# 7segement4digits1badidea-huge-digits-mk-.net
KiCad netlist of a schematic drawn in EAGLE
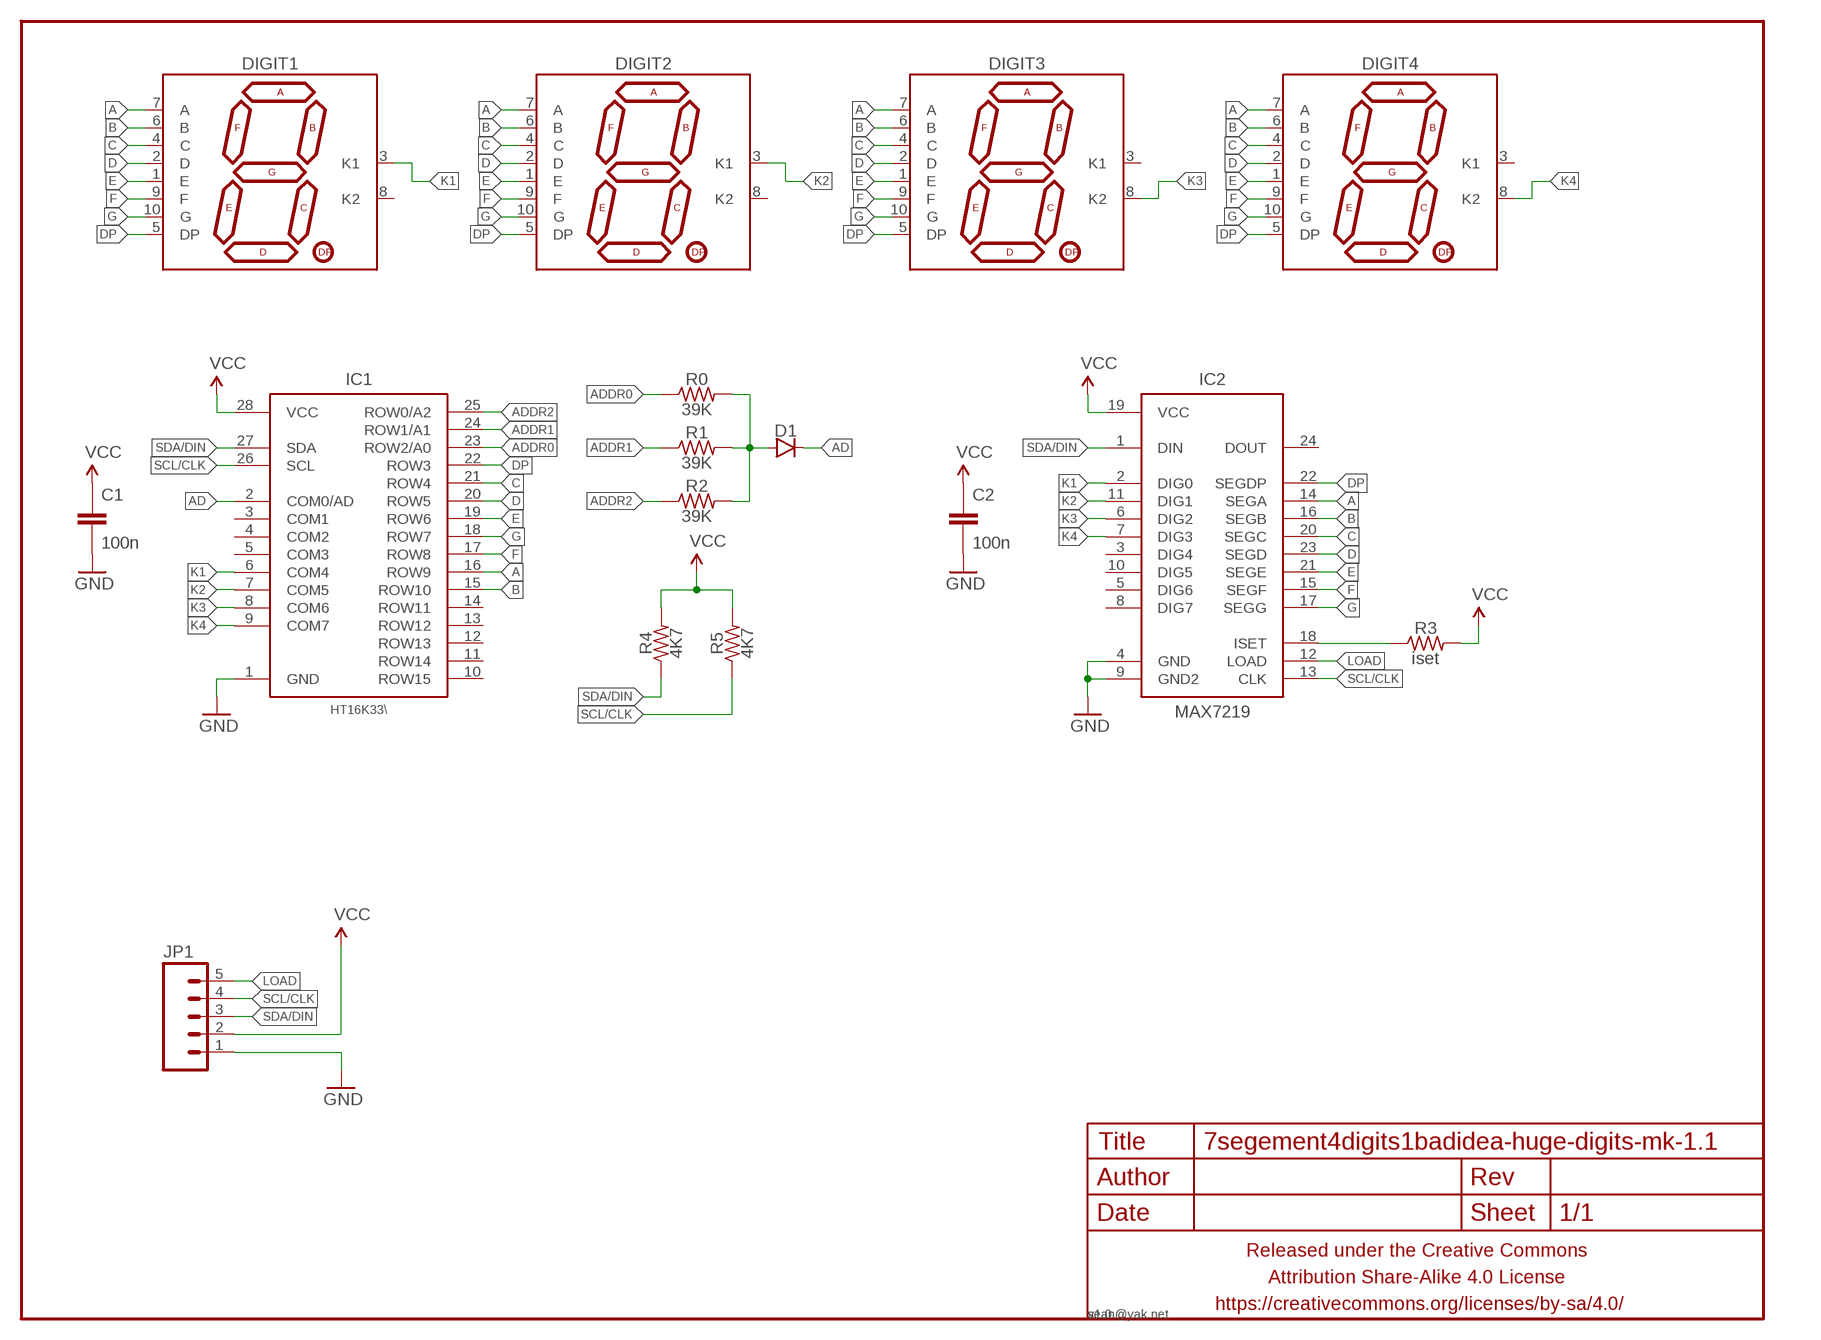
[diagram p0: schematic, sheet 1]

(export (version "E")
  (design (tool "Eeschema 10.0.6"))
  (components
    (comp (ref "C1")
      (value "100n")
      (footprint "eagle-import:C0805")
      (libsource (lib "eagle-import") (part "CAPACITOR-CERAMICC0805"))
    )
    (comp (ref "C2")
      (value "100n")
      (footprint "eagle-import:C0805")
      (libsource (lib "eagle-import") (part "CAPACITOR-CERAMICC0805"))
    )
    (comp (ref "D1")
      (value "DIODESOD123")
      (footprint "eagle-import:SOD123")
      (libsource (lib "eagle-import") (part "DIODESOD123"))
    )
    (comp (ref "DIGIT1")
      (value "7SEG_1DIGPTH-25.4MM")
      (footprint "eagle-import:7SEG_1DIG_25.4MM")
      (libsource (lib "eagle-import") (part "7SEG_1DIGPTH-25.4MM"))
    )
    (comp (ref "DIGIT2")
      (value "7SEG_1DIGPTH-25.4MM")
      (footprint "eagle-import:7SEG_1DIG_25.4MM")
      (libsource (lib "eagle-import") (part "7SEG_1DIGPTH-25.4MM"))
    )
    (comp (ref "DIGIT3")
      (value "7SEG_1DIGPTH-25.4MM")
      (footprint "eagle-import:7SEG_1DIG_25.4MM")
      (libsource (lib "eagle-import") (part "7SEG_1DIGPTH-25.4MM"))
    )
    (comp (ref "DIGIT4")
      (value "7SEG_1DIGPTH-25.4MM")
      (footprint "eagle-import:7SEG_1DIG_25.4MM")
      (libsource (lib "eagle-import") (part "7SEG_1DIGPTH-25.4MM"))
    )
    (comp (ref "FRAME1")
      (value "FRAME-LETTERNO_PACKAGE")
      (footprint "eagle-import:DUMMY")
      (fields
        (field (name "DESIGNER") "Nobody")
        (field (name "VERSION") "v01")
        (field (name "DESIGNER_1") "sean@yak.net")
        (field (name "VERSION_1") "v1.0")
      )
      (libsource (lib "eagle-import") (part "FRAME-LETTERNO_PACKAGE"))
    )
    (comp (ref "IC1")
      (value "HT16K33\\")
      (footprint "eagle-import:SOIC28W")
      (libsource (lib "eagle-import") (part "HT16K33-28SOIC28W"))
    )
    (comp (ref "IC2")
      (value "MAX7219")
      (footprint "eagle-import:SO24W")
      (libsource (lib "eagle-import") (part "MAX7219SOIC-W"))
    )
    (comp (ref "JP1")
      (value "M05PTH-CENTERED")
      (footprint "eagle-import:1X05_PTH_CENTERED")
      (libsource (lib "eagle-import") (part "M05PTH-CENTERED"))
    )
    (comp (ref "R0")
      (value "39K")
      (footprint "eagle-import:R0805")
      (libsource (lib "eagle-import") (part "RESISTORR0805"))
    )
    (comp (ref "R1")
      (value "39K")
      (footprint "eagle-import:R0805")
      (libsource (lib "eagle-import") (part "RESISTORR0805"))
    )
    (comp (ref "R2")
      (value "39K")
      (footprint "eagle-import:R0805")
      (libsource (lib "eagle-import") (part "RESISTORR0805"))
    )
    (comp (ref "R3")
      (value "iset")
      (footprint "eagle-import:R0805")
      (libsource (lib "eagle-import") (part "RESISTORR0805"))
    )
    (comp (ref "R4")
      (value "4K7")
      (footprint "eagle-import:R0805")
      (libsource (lib "eagle-import") (part "RESISTORR0805"))
    )
    (comp (ref "R5")
      (value "4K7")
      (footprint "eagle-import:R0805")
      (libsource (lib "eagle-import") (part "RESISTORR0805"))
    )
  )
  (nets
    (net (code "1") (name "A") (class "Default")
      (node (ref "DIGIT1") (pin "7") (pinfunction "A_7") (pintype "bidirectional"))
      (node (ref "DIGIT2") (pin "7") (pinfunction "A_7") (pintype "bidirectional"))
      (node (ref "DIGIT3") (pin "7") (pinfunction "A_7") (pintype "bidirectional"))
      (node (ref "DIGIT4") (pin "7") (pinfunction "A_7") (pintype "bidirectional"))
      (node (ref "IC1") (pin "16") (pinfunction "ROW9_16") (pintype "bidirectional"))
      (node (ref "IC2") (pin "14") (pinfunction "SEGA_14") (pintype "bidirectional"))
    )
    (net (code "2") (name "AD") (class "Default")
      (node (ref "D1") (pin "C") (pinfunction "C_C") (pintype "passive"))
      (node (ref "IC1") (pin "2") (pinfunction "COM0/AD_2") (pintype "bidirectional"))
    )
    (net (code "3") (name "ADDR0") (class "Default")
      (node (ref "IC1") (pin "23") (pinfunction "ROW2/A0_23") (pintype "bidirectional"))
      (node (ref "R0") (pin "1") (pinfunction "1_1") (pintype "passive"))
    )
    (net (code "4") (name "ADDR1") (class "Default")
      (node (ref "IC1") (pin "24") (pinfunction "ROW1/A1_24") (pintype "bidirectional"))
      (node (ref "R1") (pin "1") (pinfunction "1_1") (pintype "passive"))
    )
    (net (code "5") (name "ADDR2") (class "Default")
      (node (ref "IC1") (pin "25") (pinfunction "ROW0/A2_25") (pintype "bidirectional"))
      (node (ref "R2") (pin "1") (pinfunction "1_1") (pintype "passive"))
    )
    (net (code "6") (name "B") (class "Default")
      (node (ref "DIGIT1") (pin "6") (pinfunction "B_6") (pintype "bidirectional"))
      (node (ref "DIGIT2") (pin "6") (pinfunction "B_6") (pintype "bidirectional"))
      (node (ref "DIGIT3") (pin "6") (pinfunction "B_6") (pintype "bidirectional"))
      (node (ref "DIGIT4") (pin "6") (pinfunction "B_6") (pintype "bidirectional"))
      (node (ref "IC1") (pin "15") (pinfunction "ROW10_15") (pintype "bidirectional"))
      (node (ref "IC2") (pin "16") (pinfunction "SEGB_16") (pintype "bidirectional"))
    )
    (net (code "7") (name "C") (class "Default")
      (node (ref "DIGIT1") (pin "4") (pinfunction "C_4") (pintype "bidirectional"))
      (node (ref "DIGIT2") (pin "4") (pinfunction "C_4") (pintype "bidirectional"))
      (node (ref "DIGIT3") (pin "4") (pinfunction "C_4") (pintype "bidirectional"))
      (node (ref "DIGIT4") (pin "4") (pinfunction "C_4") (pintype "bidirectional"))
      (node (ref "IC1") (pin "21") (pinfunction "ROW4_21") (pintype "bidirectional"))
      (node (ref "IC2") (pin "20") (pinfunction "SEGC_20") (pintype "bidirectional"))
    )
    (net (code "8") (name "D") (class "Default")
      (node (ref "DIGIT1") (pin "2") (pinfunction "D_2") (pintype "bidirectional"))
      (node (ref "DIGIT2") (pin "2") (pinfunction "D_2") (pintype "bidirectional"))
      (node (ref "DIGIT3") (pin "2") (pinfunction "D_2") (pintype "bidirectional"))
      (node (ref "DIGIT4") (pin "2") (pinfunction "D_2") (pintype "bidirectional"))
      (node (ref "IC1") (pin "20") (pinfunction "ROW5_20") (pintype "bidirectional"))
      (node (ref "IC2") (pin "23") (pinfunction "SEGD_23") (pintype "bidirectional"))
    )
    (net (code "9") (name "DP") (class "Default")
      (node (ref "DIGIT1") (pin "5") (pinfunction "DP_5") (pintype "bidirectional"))
      (node (ref "DIGIT2") (pin "5") (pinfunction "DP_5") (pintype "bidirectional"))
      (node (ref "DIGIT3") (pin "5") (pinfunction "DP_5") (pintype "bidirectional"))
      (node (ref "DIGIT4") (pin "5") (pinfunction "DP_5") (pintype "bidirectional"))
      (node (ref "IC1") (pin "22") (pinfunction "ROW3_22") (pintype "bidirectional"))
      (node (ref "IC2") (pin "22") (pinfunction "SEGDP_22") (pintype "bidirectional"))
    )
    (net (code "10") (name "E") (class "Default")
      (node (ref "DIGIT1") (pin "1") (pinfunction "E_1") (pintype "bidirectional"))
      (node (ref "DIGIT2") (pin "1") (pinfunction "E_1") (pintype "bidirectional"))
      (node (ref "DIGIT3") (pin "1") (pinfunction "E_1") (pintype "bidirectional"))
      (node (ref "DIGIT4") (pin "1") (pinfunction "E_1") (pintype "bidirectional"))
      (node (ref "IC1") (pin "19") (pinfunction "ROW6_19") (pintype "bidirectional"))
      (node (ref "IC2") (pin "21") (pinfunction "SEGE_21") (pintype "bidirectional"))
    )
    (net (code "11") (name "F") (class "Default")
      (node (ref "DIGIT1") (pin "9") (pinfunction "F_9") (pintype "bidirectional"))
      (node (ref "DIGIT2") (pin "9") (pinfunction "F_9") (pintype "bidirectional"))
      (node (ref "DIGIT3") (pin "9") (pinfunction "F_9") (pintype "bidirectional"))
      (node (ref "DIGIT4") (pin "9") (pinfunction "F_9") (pintype "bidirectional"))
      (node (ref "IC1") (pin "17") (pinfunction "ROW8_17") (pintype "bidirectional"))
      (node (ref "IC2") (pin "15") (pinfunction "SEGF_15") (pintype "bidirectional"))
    )
    (net (code "12") (name "G") (class "Default")
      (node (ref "DIGIT1") (pin "10") (pinfunction "G_10") (pintype "bidirectional"))
      (node (ref "DIGIT2") (pin "10") (pinfunction "G_10") (pintype "bidirectional"))
      (node (ref "DIGIT3") (pin "10") (pinfunction "G_10") (pintype "bidirectional"))
      (node (ref "DIGIT4") (pin "10") (pinfunction "G_10") (pintype "bidirectional"))
      (node (ref "IC1") (pin "18") (pinfunction "ROW7_18") (pintype "bidirectional"))
      (node (ref "IC2") (pin "17") (pinfunction "SEGG_17") (pintype "bidirectional"))
    )
    (net (code "13") (name "GND") (class "Default")
      (node (ref "C1") (pin "2") (pinfunction "2_2") (pintype "passive"))
      (node (ref "C2") (pin "2") (pinfunction "2_2") (pintype "passive"))
      (node (ref "IC1") (pin "1") (pinfunction "GND_1") (pintype "bidirectional"))
      (node (ref "IC2") (pin "4") (pinfunction "GND_4") (pintype "bidirectional"))
      (node (ref "IC2") (pin "9") (pinfunction "GND2_9") (pintype "bidirectional"))
      (node (ref "JP1") (pin "1") (pinfunction "1_1") (pintype "passive"))
    )
    (net (code "14") (name "K1") (class "Default")
      (node (ref "DIGIT1") (pin "3") (pinfunction "K1_3") (pintype "bidirectional"))
      (node (ref "IC1") (pin "6") (pinfunction "COM4_6") (pintype "bidirectional"))
      (node (ref "IC2") (pin "2") (pinfunction "DIG0_2") (pintype "bidirectional"))
    )
    (net (code "15") (name "K2") (class "Default")
      (node (ref "DIGIT2") (pin "3") (pinfunction "K1_3") (pintype "bidirectional"))
      (node (ref "IC1") (pin "7") (pinfunction "COM5_7") (pintype "bidirectional"))
      (node (ref "IC2") (pin "11") (pinfunction "DIG1_11") (pintype "bidirectional"))
    )
    (net (code "16") (name "K3") (class "Default")
      (node (ref "DIGIT3") (pin "8") (pinfunction "K2_8") (pintype "bidirectional"))
      (node (ref "IC1") (pin "8") (pinfunction "COM6_8") (pintype "bidirectional"))
      (node (ref "IC2") (pin "6") (pinfunction "DIG2_6") (pintype "bidirectional"))
    )
    (net (code "17") (name "K4") (class "Default")
      (node (ref "DIGIT4") (pin "8") (pinfunction "K2_8") (pintype "bidirectional"))
      (node (ref "IC1") (pin "9") (pinfunction "COM7_9") (pintype "bidirectional"))
      (node (ref "IC2") (pin "7") (pinfunction "DIG3_7") (pintype "bidirectional"))
    )
    (net (code "18") (name "LOAD") (class "Default")
      (node (ref "IC2") (pin "12") (pinfunction "LOAD_12") (pintype "bidirectional"))
      (node (ref "JP1") (pin "5") (pinfunction "5_5") (pintype "passive"))
    )
    (net (code "19") (name "Net-(D1-PadA)") (class "Default")
      (node (ref "D1") (pin "A") (pinfunction "A_A") (pintype "passive"))
      (node (ref "R0") (pin "2") (pinfunction "2_2") (pintype "passive"))
      (node (ref "R1") (pin "2") (pinfunction "2_2") (pintype "passive"))
      (node (ref "R2") (pin "2") (pinfunction "2_2") (pintype "passive"))
    )
    (net (code "20") (name "Net-(IC2-ISET)") (class "Default")
      (node (ref "IC2") (pin "18") (pinfunction "ISET_18") (pintype "bidirectional"))
      (node (ref "R3") (pin "1") (pinfunction "1_1") (pintype "passive"))
    )
    (net (code "21") (name "SCL{slash}CLK") (class "Default")
      (node (ref "IC1") (pin "26") (pinfunction "SCL_26") (pintype "bidirectional"))
      (node (ref "IC2") (pin "13") (pinfunction "CLK_13") (pintype "bidirectional"))
      (node (ref "JP1") (pin "4") (pinfunction "4_4") (pintype "passive"))
      (node (ref "R5") (pin "1") (pinfunction "1_1") (pintype "passive"))
    )
    (net (code "22") (name "SDA{slash}DIN") (class "Default")
      (node (ref "IC1") (pin "27") (pinfunction "SDA_27") (pintype "bidirectional"))
      (node (ref "IC2") (pin "1") (pinfunction "DIN_1") (pintype "bidirectional"))
      (node (ref "JP1") (pin "3") (pinfunction "3_3") (pintype "passive"))
      (node (ref "R4") (pin "1") (pinfunction "1_1") (pintype "passive"))
    )
    (net (code "23") (name "VCC") (class "Default")
      (node (ref "C1") (pin "1") (pinfunction "1_1") (pintype "passive"))
      (node (ref "C2") (pin "1") (pinfunction "1_1") (pintype "passive"))
      (node (ref "IC1") (pin "28") (pinfunction "VCC_28") (pintype "bidirectional"))
      (node (ref "IC2") (pin "19") (pinfunction "VCC_19") (pintype "bidirectional"))
      (node (ref "JP1") (pin "2") (pinfunction "2_2") (pintype "passive"))
      (node (ref "R3") (pin "2") (pinfunction "2_2") (pintype "passive"))
      (node (ref "R4") (pin "2") (pinfunction "2_2") (pintype "passive"))
      (node (ref "R5") (pin "2") (pinfunction "2_2") (pintype "passive"))
    )
    (net (code "24") (name "unconnected-(DIGIT1-K2-Pad8)") (class "Default")
      (node (ref "DIGIT1") (pin "8") (pinfunction "K2_8") (pintype "bidirectional"))
    )
    (net (code "25") (name "unconnected-(DIGIT2-K2-Pad8)") (class "Default")
      (node (ref "DIGIT2") (pin "8") (pinfunction "K2_8") (pintype "bidirectional"))
    )
    (net (code "26") (name "unconnected-(DIGIT3-K1-Pad3)") (class "Default")
      (node (ref "DIGIT3") (pin "3") (pinfunction "K1_3") (pintype "bidirectional"))
    )
    (net (code "27") (name "unconnected-(DIGIT4-K1-Pad3)") (class "Default")
      (node (ref "DIGIT4") (pin "3") (pinfunction "K1_3") (pintype "bidirectional"))
    )
    (net (code "28") (name "unconnected-(IC1-COM1-Pad3)") (class "Default")
      (node (ref "IC1") (pin "3") (pinfunction "COM1_3") (pintype "bidirectional"))
    )
    (net (code "29") (name "unconnected-(IC1-COM2-Pad4)") (class "Default")
      (node (ref "IC1") (pin "4") (pinfunction "COM2_4") (pintype "bidirectional"))
    )
    (net (code "30") (name "unconnected-(IC1-COM3-Pad5)") (class "Default")
      (node (ref "IC1") (pin "5") (pinfunction "COM3_5") (pintype "bidirectional"))
    )
    (net (code "31") (name "unconnected-(IC1-ROW11-Pad14)") (class "Default")
      (node (ref "IC1") (pin "14") (pinfunction "ROW11_14") (pintype "bidirectional"))
    )
    (net (code "32") (name "unconnected-(IC1-ROW12-Pad13)") (class "Default")
      (node (ref "IC1") (pin "13") (pinfunction "ROW12_13") (pintype "bidirectional"))
    )
    (net (code "33") (name "unconnected-(IC1-ROW13-Pad12)") (class "Default")
      (node (ref "IC1") (pin "12") (pinfunction "ROW13_12") (pintype "bidirectional"))
    )
    (net (code "34") (name "unconnected-(IC1-ROW14-Pad11)") (class "Default")
      (node (ref "IC1") (pin "11") (pinfunction "ROW14_11") (pintype "bidirectional"))
    )
    (net (code "35") (name "unconnected-(IC1-ROW15-Pad10)") (class "Default")
      (node (ref "IC1") (pin "10") (pinfunction "ROW15_10") (pintype "bidirectional"))
    )
    (net (code "36") (name "unconnected-(IC2-DIG4-Pad3)") (class "Default")
      (node (ref "IC2") (pin "3") (pinfunction "DIG4_3") (pintype "bidirectional"))
    )
    (net (code "37") (name "unconnected-(IC2-DIG5-Pad10)") (class "Default")
      (node (ref "IC2") (pin "10") (pinfunction "DIG5_10") (pintype "bidirectional"))
    )
    (net (code "38") (name "unconnected-(IC2-DIG6-Pad5)") (class "Default")
      (node (ref "IC2") (pin "5") (pinfunction "DIG6_5") (pintype "bidirectional"))
    )
    (net (code "39") (name "unconnected-(IC2-DIG7-Pad8)") (class "Default")
      (node (ref "IC2") (pin "8") (pinfunction "DIG7_8") (pintype "bidirectional"))
    )
    (net (code "40") (name "unconnected-(IC2-DOUT-Pad24)") (class "Default")
      (node (ref "IC2") (pin "24") (pinfunction "DOUT_24") (pintype "bidirectional"))
    )
  )
)
